# ElectronicSpeedRegulator.net
KiCad netlist of a schematic drawn in EAGLE
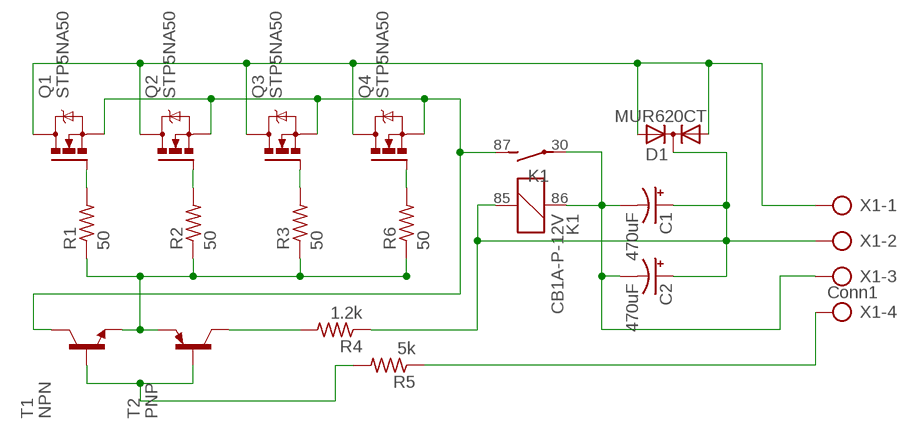
[diagram p0: schematic, sheet 1]

(export (version "E")
  (design (tool "Eeschema 10.0.6"))
  (components
    (comp (ref "C1")
      (value "470uF")
      (footprint "eagle-import:E5-13")
      (libsource (lib "eagle-import") (part "CPOL-USE5-13"))
    )
    (comp (ref "C2")
      (value "470uF")
      (footprint "eagle-import:E5-13")
      (libsource (lib "eagle-import") (part "CPOL-USE5-13"))
    )
    (comp (ref "D1")
      (value "MUR620CT")
      (footprint "eagle-import:TO220AB")
      (libsource (lib "eagle-import") (part "MUR620CT"))
    )
    (comp (ref "K1")
      (value "CB1A-P-12V")
      (footprint "eagle-import:CB1")
      (fields (field (name "MF") "AROMAT/ MATSUSHITA"))
      (libsource (lib "eagle-import") (part "CB1A-P-12V"))
    )
    (comp (ref "Q1")
      (value "STP5NA50")
      (footprint "eagle-import:TO220BV")
      (libsource (lib "eagle-import") (part "STP5NA50"))
    )
    (comp (ref "Q2")
      (value "STP5NA50")
      (footprint "eagle-import:TO220BV")
      (libsource (lib "eagle-import") (part "STP5NA50"))
    )
    (comp (ref "Q3")
      (value "STP5NA50")
      (footprint "eagle-import:TO220BV")
      (libsource (lib "eagle-import") (part "STP5NA50"))
    )
    (comp (ref "Q4")
      (value "STP5NA50")
      (footprint "eagle-import:TO220BV")
      (libsource (lib "eagle-import") (part "STP5NA50"))
    )
    (comp (ref "R1")
      (value "50")
      (footprint "eagle-import:0204_7")
      (libsource (lib "eagle-import") (part "R-US_0204/7"))
    )
    (comp (ref "R2")
      (value "50")
      (footprint "eagle-import:0204_7")
      (libsource (lib "eagle-import") (part "R-US_0204/7"))
    )
    (comp (ref "R3")
      (value "50")
      (footprint "eagle-import:0204_7")
      (libsource (lib "eagle-import") (part "R-US_0204/7"))
    )
    (comp (ref "R4")
      (value "1.2k")
      (footprint "eagle-import:0204_7")
      (libsource (lib "eagle-import") (part "R-US_0204/7"))
    )
    (comp (ref "R5")
      (value "5k")
      (footprint "eagle-import:0204_7")
      (libsource (lib "eagle-import") (part "R-US_0204/7"))
    )
    (comp (ref "R6")
      (value "50")
      (footprint "eagle-import:0204_7")
      (libsource (lib "eagle-import") (part "R-US_0204/7"))
    )
    (comp (ref "T1")
      (value "NPN")
      (footprint "eagle-import:TO92-EBC")
      (libsource (lib "eagle-import") (part "-NPN-TO92-EBC"))
    )
    (comp (ref "T2")
      (value "PNP")
      (footprint "eagle-import:TO92-EBC")
      (libsource (lib "eagle-import") (part "-PNP-TO92-EBCBC327-16"))
    )
    (comp (ref "X1")
      (value "Conn1")
      (footprint "eagle-import:AK300_4")
      (libsource (lib "eagle-import") (part "AK300/4"))
    )
  )
  (nets
    (net (code "1") (name "Net-(K1A-1)") (class "Default")
      (node (ref "C1") (pin "-") (pinfunction "-_-") (pintype "passive"))
      (node (ref "C2") (pin "-") (pinfunction "-_-") (pintype "passive"))
      (node (ref "K1") (pin "30") (pinfunction "P_30") (pintype "passive"))
      (node (ref "K1") (pin "86") (pinfunction "1_86") (pintype "passive"))
      (node (ref "X1") (pin "3") (pinfunction "KL_3") (pintype "passive"))
    )
    (net (code "2") (name "Net-(K1A-2)") (class "Default")
      (node (ref "C1") (pin "+") (pinfunction "+_+") (pintype "passive"))
      (node (ref "C2") (pin "+") (pinfunction "+_+") (pintype "passive"))
      (node (ref "D1") (pin "C") (pinfunction "C_C") (pintype "passive"))
      (node (ref "K1") (pin "85") (pinfunction "2_85") (pintype "passive"))
      (node (ref "R4") (pin "1") (pinfunction "1_1") (pintype "passive"))
      (node (ref "X1") (pin "2") (pinfunction "KL_2") (pintype "passive"))
    )
    (net (code "3") (name "Net-(K1B-S)") (class "Default")
      (node (ref "K1") (pin "87") (pinfunction "S_87") (pintype "passive"))
      (node (ref "Q1") (pin "S") (pinfunction "S_S") (pintype "passive"))
      (node (ref "Q2") (pin "S") (pinfunction "S_S") (pintype "passive"))
      (node (ref "Q3") (pin "S") (pinfunction "S_S") (pintype "passive"))
      (node (ref "Q4") (pin "S") (pinfunction "S_S") (pintype "passive"))
      (node (ref "T1") (pin "C") (pinfunction "C_C") (pintype "passive"))
    )
    (net (code "4") (name "Net-(Q1-PadG)") (class "Default")
      (node (ref "Q1") (pin "G") (pinfunction "G_G") (pintype "passive"))
      (node (ref "R1") (pin "2") (pinfunction "2_2") (pintype "passive"))
    )
    (net (code "5") (name "Net-(Q2-PadG)") (class "Default")
      (node (ref "Q2") (pin "G") (pinfunction "G_G") (pintype "passive"))
      (node (ref "R2") (pin "2") (pinfunction "2_2") (pintype "passive"))
    )
    (net (code "6") (name "Net-(Q3-PadG)") (class "Default")
      (node (ref "Q3") (pin "G") (pinfunction "G_G") (pintype "passive"))
      (node (ref "R3") (pin "2") (pinfunction "2_2") (pintype "passive"))
    )
    (net (code "7") (name "Net-(Q4-PadG)") (class "Default")
      (node (ref "Q4") (pin "G") (pinfunction "G_G") (pintype "passive"))
      (node (ref "R6") (pin "2") (pinfunction "2_2") (pintype "passive"))
    )
    (net (code "8") (name "Net-(R1-Pad1)") (class "Default")
      (node (ref "R1") (pin "1") (pinfunction "1_1") (pintype "passive"))
      (node (ref "R2") (pin "1") (pinfunction "1_1") (pintype "passive"))
      (node (ref "R3") (pin "1") (pinfunction "1_1") (pintype "passive"))
      (node (ref "R6") (pin "1") (pinfunction "1_1") (pintype "passive"))
      (node (ref "T1") (pin "E") (pinfunction "E_E") (pintype "passive"))
      (node (ref "T2") (pin "E") (pinfunction "E_E") (pintype "passive"))
    )
    (net (code "9") (name "Net-(R4-Pad2)") (class "Default")
      (node (ref "R4") (pin "2") (pinfunction "2_2") (pintype "passive"))
      (node (ref "T2") (pin "C") (pinfunction "C_C") (pintype "passive"))
    )
    (net (code "10") (name "Net-(R5-Pad2)") (class "Default")
      (node (ref "R5") (pin "2") (pinfunction "2_2") (pintype "passive"))
      (node (ref "T1") (pin "B") (pinfunction "B_B") (pintype "passive"))
      (node (ref "T2") (pin "B") (pinfunction "B_B") (pintype "passive"))
    )
    (net (code "11") (name "Net-(X1A-KL)") (class "Default")
      (node (ref "D1") (pin "A1") (pinfunction "A1_A1") (pintype "passive"))
      (node (ref "D1") (pin "A2") (pinfunction "A2_A2") (pintype "passive"))
      (node (ref "Q1") (pin "D") (pinfunction "D_D") (pintype "passive"))
      (node (ref "Q2") (pin "D") (pinfunction "D_D") (pintype "passive"))
      (node (ref "Q3") (pin "D") (pinfunction "D_D") (pintype "passive"))
      (node (ref "Q4") (pin "D") (pinfunction "D_D") (pintype "passive"))
      (node (ref "X1") (pin "1") (pinfunction "KL_1") (pintype "passive"))
    )
    (net (code "12") (name "Net-(X1D-KL)") (class "Default")
      (node (ref "R5") (pin "1") (pinfunction "1_1") (pintype "passive"))
      (node (ref "X1") (pin "4") (pinfunction "KL_4") (pintype "passive"))
    )
  )
)
